# Wacky_Hat_Schematic.net
KiCad netlist of a schematic drawn in Altium Designer
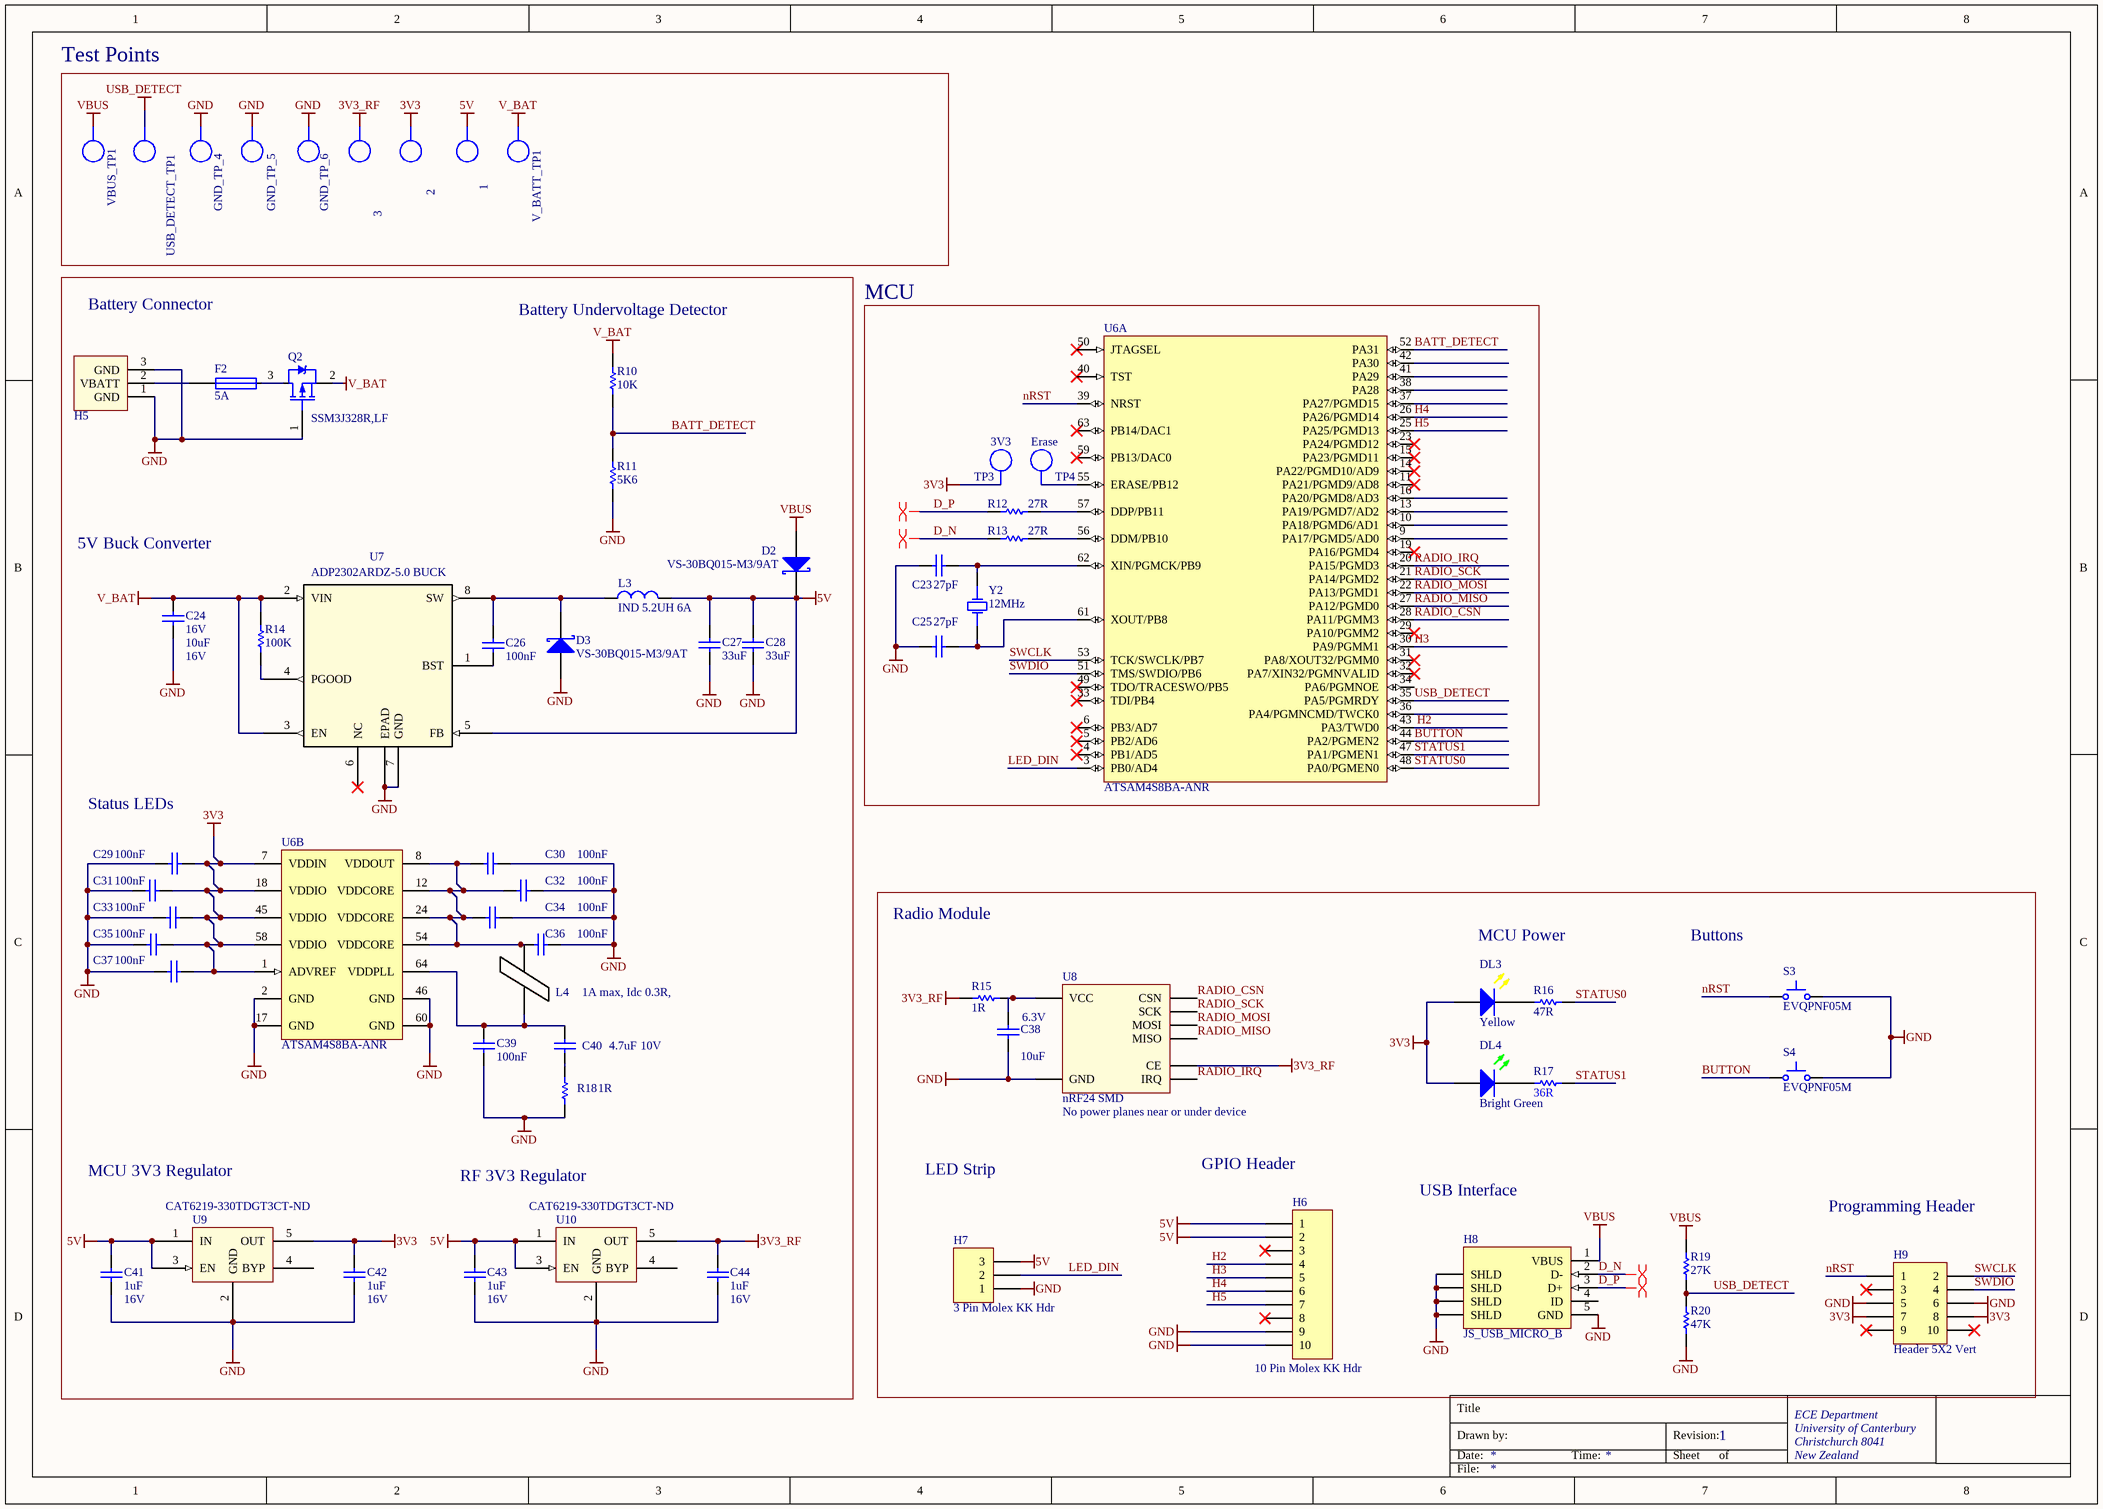
[diagram p0: Wacky Hat Schematic.SchDoc]

(export (version "E")
  (design (tool "Eeschema 10.0.6"))
  (components
    (comp (ref "1")
      (value "TP")
      (footprint "TP_1206")
      (description "Test-Point 3.3x1.6x2.1mm SMD")
      (fields
        (field (name "MANUFACTURER") "Harwin Inc")
        (field (name "MANUFACTURER PART NUMBER") "S1751-46R")
      )
      (libsource (lib "ECE AD19Components_19V1") (part "TP_1206"))
    )
    (comp (ref "2")
      (value "TP")
      (footprint "TP_1206")
      (description "Test-Point 3.3x1.6x2.1mm SMD")
      (fields
        (field (name "MANUFACTURER") "Harwin Inc")
        (field (name "MANUFACTURER PART NUMBER") "S1751-46R")
      )
      (libsource (lib "ECE AD19Components_19V1") (part "TP_1206"))
    )
    (comp (ref "3")
      (value "TP")
      (footprint "TP_1206")
      (description "Test-Point 3.3x1.6x2.1mm SMD")
      (fields
        (field (name "MANUFACTURER") "Harwin Inc")
        (field (name "MANUFACTURER PART NUMBER") "S1751-46R")
      )
      (libsource (lib "ECE AD19Components_19V1") (part "TP_1206"))
    )
    (comp (ref "C23")
      (value "27pF")
      (footprint "CAPC1608L")
      (description "CAP CER 27pF NPO/COG +-5% 50V 0603")
      (libsource (lib "ECE AD19Components_19V1") (part "CC_27pF_0603"))
    )
    (comp (ref "C24")
      (value "10uF")
      (footprint "CAPC2012L")
      (description "CAP CER 10uF X5R 16V 0805")
      (fields
        (field (name "MANUFACTURER") "Samsung Electro-Mechanics")
        (field (name "MANUFACTURER PART NUMBER") "CL21A106KOQNNWE")
        (field (name "VOLTAGE - RATED") "16V")
        (field (name "MAX VOLTAGE") "16V")
      )
      (libsource (lib "ENCE461AD19_19V2") (part "CC_10uF_16V_0805"))
    )
    (comp (ref "C25")
      (value "27pF")
      (footprint "CAPC1608L")
      (description "CAP CER 27pF NPO/COG +-5% 50V 0603")
      (libsource (lib "ECE AD19Components_19V1") (part "CC_27pF_0603"))
    )
    (comp (ref "C26")
      (value "100nF")
      (footprint "CAPC1608L")
      (description "CAP CER 100nF X7R +-10% 50V 0603")
      (libsource (lib "ECE AD19Components_19V1") (part "CC_100nF_0603"))
    )
    (comp (ref "C27")
      (value "33uF")
      (footprint "CAPC2012L")
      (description "CAP CER 33uF X5R 6V3 0805")
      (fields
        (field (name "MANUFACTURER") "TDK Corporation")
        (field (name "MANUFACTURER PART NUMBER") "C2012X5R0J336M125AC")
      )
      (libsource (lib "ENCE461AD19_19V2") (part "CC_33uF_6V3_0805"))
    )
    (comp (ref "C28")
      (value "33uF")
      (footprint "CAPC2012L")
      (description "CAP CER 33uF X5R 6V3 0805")
      (fields
        (field (name "MANUFACTURER") "TDK Corporation")
        (field (name "MANUFACTURER PART NUMBER") "C2012X5R0J336M125AC")
      )
      (libsource (lib "ENCE461AD19_19V2") (part "CC_33uF_6V3_0805"))
    )
    (comp (ref "C29")
      (value "100nF")
      (footprint "CAPC1608L")
      (description "CAP CER 100nF X7R +-10% 50V 0603")
      (libsource (lib "ECE AD19Components_19V1") (part "CC_100nF_0603"))
    )
    (comp (ref "C30")
      (value "100nF")
      (footprint "CAPC1608L")
      (description "CAP CER 100nF X7R +-10% 50V 0603")
      (libsource (lib "ECE AD19Components_19V1") (part "CC_100nF_0603"))
    )
    (comp (ref "C31")
      (value "100nF")
      (footprint "CAPC1608L")
      (description "CAP CER 100nF X7R +-10% 50V 0603")
      (libsource (lib "ECE AD19Components_19V1") (part "CC_100nF_0603"))
    )
    (comp (ref "C32")
      (value "100nF")
      (footprint "CAPC1608L")
      (description "CAP CER 100nF X7R +-10% 50V 0603")
      (libsource (lib "ECE AD19Components_19V1") (part "CC_100nF_0603"))
    )
    (comp (ref "C33")
      (value "100nF")
      (footprint "CAPC1608L")
      (description "CAP CER 100nF X7R +-10% 50V 0603")
      (libsource (lib "ECE AD19Components_19V1") (part "CC_100nF_0603"))
    )
    (comp (ref "C34")
      (value "100nF")
      (footprint "CAPC1608L")
      (description "CAP CER 100nF X7R +-10% 50V 0603")
      (libsource (lib "ECE AD19Components_19V1") (part "CC_100nF_0603"))
    )
    (comp (ref "C35")
      (value "100nF")
      (footprint "CAPC1608L")
      (description "CAP CER 100nF X7R +-10% 50V 0603")
      (libsource (lib "ECE AD19Components_19V1") (part "CC_100nF_0603"))
    )
    (comp (ref "C36")
      (value "100nF")
      (footprint "CAPC1608L")
      (description "CAP CER 100nF X7R +-10% 50V 0603")
      (libsource (lib "ECE AD19Components_19V1") (part "CC_100nF_0603"))
    )
    (comp (ref "C37")
      (value "100nF")
      (footprint "CAPC1608L")
      (description "CAP CER 100nF X7R +-10% 50V 0603")
      (libsource (lib "ECE AD19Components_19V1") (part "CC_100nF_0603"))
    )
    (comp (ref "C38")
      (value "10uF")
      (footprint "CAPC1608L")
      (description "CAP CER 10UF X5R +-20% 6V3 0603")
      (fields (field (name "VOLTAGE - RATED") "6.3V"))
      (libsource (lib "ECE AD19Components_19V1") (part "CC_10uF_0603"))
    )
    (comp (ref "C39")
      (value "100nF")
      (footprint "CAPC1608L")
      (description "CAP CER 100nF X7R +-10% 50V 0603")
      (libsource (lib "ECE AD19Components_19V1") (part "CC_100nF_0603"))
    )
    (comp (ref "C40")
      (value "4.7uF")
      (footprint "CAPC1608N")
      (description "CAP CER 4.7uF X5R +-20%  10V 0603")
      (fields (field (name "MAX VOLTAGE") "10V"))
      (libsource (lib "ECE AD19Components_19V1") (part "CC_4.7uF_0603"))
    )
    (comp (ref "C41")
      (value "1uF")
      (footprint "CAPC1608L")
      (description "CAP CER 1uF Y5V -20% +80% 16V 0603")
      (fields (field (name "MAX VOLTAGE") "16V"))
      (libsource (lib "ECE AD19Components_19V1") (part "CC_1uF_0603"))
    )
    (comp (ref "C42")
      (value "1uF")
      (footprint "CAPC1608L")
      (description "CAP CER 1uF Y5V -20% +80% 16V 0603")
      (fields (field (name "MAX VOLTAGE") "16V"))
      (libsource (lib "ECE AD19Components_19V1") (part "CC_1uF_0603"))
    )
    (comp (ref "C43")
      (value "1uF")
      (footprint "CAPC1608L")
      (description "CAP CER 1uF Y5V -20% +80% 16V 0603")
      (fields (field (name "MAX VOLTAGE") "16V"))
      (libsource (lib "ECE AD19Components_19V1") (part "CC_1uF_0603"))
    )
    (comp (ref "C44")
      (value "1uF")
      (footprint "CAPC1608L")
      (description "CAP CER 1uF Y5V -20% +80% 16V 0603")
      (fields (field (name "MAX VOLTAGE") "16V"))
      (libsource (lib "ECE AD19Components_19V1") (part "CC_1uF_0603"))
    )
    (comp (ref "D2")
      (value "VS-30BQ015-M3/9AT")
      (footprint "SMC")
      (description "DIODE, SCHOTTKY, 3A, 15V, DO-214AB / SMC")
      (fields (field (name "MANUFACTURER") "Vishay Semiconductors"))
      (libsource (lib "ECE AD19Components_19V1") (part "DS_VS-30BQ015-M3"))
    )
    (comp (ref "D3")
      (value "VS-30BQ015-M3/9AT")
      (footprint "SMC")
      (description "DIODE, SCHOTTKY, 3A, 15V, DO-214AB / SMC")
      (fields (field (name "MANUFACTURER") "Vishay Semiconductors"))
      (libsource (lib "ECE AD19Components_19V1") (part "DS_VS-30BQ015-M3"))
    )
    (comp (ref "DL3")
      (value "Yellow")
      (footprint "WL-SMCW0603")
      (description "LED Yellow 120mcd 0603 SMD")
      (fields
        (field (name "MANUFACTURER") "WURTH ELEKTRONIK")
        (field (name "MANUFACTURER PART NUMBER") "150060YS75000")
        (field (name "LED COLOUR") "Yellow")
      )
      (libsource (lib "ECE AD19Components_19V1") (part "DL_150060YS75000"))
    )
    (comp (ref "DL4")
      (value "Bright Green")
      (footprint "WL-SMCW0603")
      (description "LED Bright Green 40mcd 0603 SMD")
      (fields
        (field (name "MANUFACTURER") "WURTH ELEKTRONIK")
        (field (name "MANUFACTURER PART NUMBER") "150060VS75000")
        (field (name "LED COLOUR") "Bright Green")
      )
      (libsource (lib "ECE AD19Components_19V1") (part "DL_150060VS75000"))
    )
    (comp (ref "F2")
      (value "5A")
      (footprint "RESC3216N")
      (description "Fuse 5.0A Fast Acting 1206 SMD")
      (fields (field (name "MANUFACTURER PART NUMBER") "C1F5") (field (name "MANUFACTURER") "Bel TRP"))
      (libsource (lib "ECE AD19Components_19V1") (part "FS_Fuse_5.0A"))
    )
    (comp (ref "GND_TP_4")
      (value "TP")
      (footprint "TP_1206")
      (description "Test-Point 3.3x1.6x2.1mm SMD")
      (fields
        (field (name "MANUFACTURER") "Harwin Inc")
        (field (name "MANUFACTURER PART NUMBER") "S1751-46R")
      )
      (libsource (lib "ECE AD19Components_19V1") (part "TP_1206"))
    )
    (comp (ref "GND_TP_5")
      (value "TP")
      (footprint "TP_1206")
      (description "Test-Point 3.3x1.6x2.1mm SMD")
      (fields
        (field (name "MANUFACTURER") "Harwin Inc")
        (field (name "MANUFACTURER PART NUMBER") "S1751-46R")
      )
      (libsource (lib "ECE AD19Components_19V1") (part "TP_1206"))
    )
    (comp (ref "GND_TP_6")
      (value "TP")
      (footprint "TP_1206")
      (description "Test-Point 3.3x1.6x2.1mm SMD")
      (fields
        (field (name "MANUFACTURER") "Harwin Inc")
        (field (name "MANUFACTURER PART NUMBER") "S1751-46R")
      )
      (libsource (lib "ECE AD19Components_19V1") (part "TP_1206"))
    )
    (comp (ref "H5")
      (value "Battery_HEADER_3pin")
      (footprint "BATT_HEADER_3POS")
      (description "3Pin Header 2.54mm spacing")
      (libsource (lib "ENCE461AD19_19V2") (part "Battery_HEADER_3pin"))
    )
    (comp (ref "H6")
      (value "10 Pin Molex KK Hdr")
      (footprint "MOLEX_KK_10_HDR")
      (description "CONN HEADER 10POS 2.54mm VERT_ Thru Hole")
      (libsource (lib "ECE AD19Components_19V1") (part "JA_MOLEX_KK_10POS"))
    )
    (comp (ref "H7")
      (value "3 Pin Molex KK Hdr")
      (footprint "MOLEX_KK_3_HDR")
      (description "CONN HEADER 3POS 2.54mm VERT_Thru Hole")
      (fields (field (name "MANUFACTURER") "Molex"))
      (libsource (lib "ECE AD19Components_19V1") (part "JA_MOLEX_KK_3POS"))
    )
    (comp (ref "H8")
      (value "JS_USB_MICRO_B")
      (footprint "FCI_USB_10118194-0001LF")
      (description "CONN USB MICRO B RECPT SMT R/A")
      (fields (field (name "MANUFACTURER") "FCI") (field (name "MANUFACTURER PART NUMBER") "10118194-0001LF"))
      (libsource (lib "ECE AD19Components_19V1") (part "JS_USB_MICRO_B_SMT"))
    )
    (comp (ref "H9")
      (value "Header 5X2 Vert")
      (footprint "IDC2.54-V10D")
      (description "IDC Header, 2,54mm, 10-Pin, Vert")
      (libsource (lib "ECE AD19Components_19V1") (part "JA_HDR_IDC_5X2_VERT"))
    )
    (comp (ref "L3")
      (value "IND 5.2UH 6A")
      (footprint "INDUCTOR5u2")
      (description "FIXED IND 5.2UH 6A 22 MOHM SMD")
      (fields
        (field (name "MANUFACTURER") "Sumida America Components Inc.")
        (field (name "MANUFACTURER PART NUMBER") "CDRH104RNP-5R2NC")
      )
      (libsource (lib "ENCE461AD19_19V2") (part "CDRH104RNP-5R2NC"))
    )
    (comp (ref "L4")
      (value "1A max, Idc 0.3R,")
      (footprint "INDC3216L")
      (description "Ferrite Bead, Rdc 0.3R, Z100MHZ 600R, Imax 1A, SMD 1206")
      (fields
        (field (name "MANUFACTURER") "FAIR-RITE")
        (field (name "MANUFACTURER PART NUMBER") "2512066017Y1")
      )
      (libsource (lib "ECE AD19Components_19V1") (part "IN_Ferrite-Bead"))
    )
    (comp (ref "Q2")
      (value "SSM3J328R,LF")
      (footprint "SOT23_L")
      (description "MOSFET P-CH 20V 6A SOT23-3")
      (fields
        (field (name "MANUFACTURER") "Toshiba")
        (field (name "MANUFACTURER PART NUMBER") "SSM3J328R,LF")
      )
      (libsource (lib "ECE AD19Components_19V1") (part "TM_SSM3J328R"))
    )
    (comp (ref "R10")
      (value "10K")
      (footprint "RESC1608L")
      (description "RES 10.0K OHM 1/10W 5% 0603 SMD")
      (libsource (lib "ECE AD19Components_19V1") (part "RS_10K"))
    )
    (comp (ref "R11")
      (value "5K6")
      (footprint "RESC1608L")
      (description "RES 5.6K OHM 1/10W 5% 0603 SMD")
      (libsource (lib "ECE AD19Components_19V1") (part "RS_5K6"))
    )
    (comp (ref "R12")
      (value "27R")
      (footprint "RESC1608L")
      (description "RES 27 OHM 1/10W 5% 0603 SMD")
      (libsource (lib "ECE AD19Components_19V1") (part "RS_27R"))
    )
    (comp (ref "R13")
      (value "27R")
      (footprint "RESC1608L")
      (description "RES 27 OHM 1/10W 5% 0603 SMD")
      (libsource (lib "ECE AD19Components_19V1") (part "RS_27R"))
    )
    (comp (ref "R14")
      (value "100K")
      (footprint "RESC1608L")
      (description "RES 100K OHM 1/10W 5% 0603 SMD")
      (libsource (lib "ECE AD19Components_19V1") (part "RS_100K"))
    )
    (comp (ref "R15")
      (value "1R")
      (footprint "RESC3216L")
      (description "RES 1R OHM 1/4W 5% 1206 SMD")
      (libsource (lib "ECE AD19Components_19V1") (part "RT_1R"))
    )
    (comp (ref "R16")
      (value "47R")
      (footprint "RESC1608L")
      (description "RES 47 OHM 1/10W 5% 0603 SMD")
      (libsource (lib "ECE AD19Components_19V1") (part "RS_47R"))
    )
    (comp (ref "R17")
      (value "36R")
      (footprint "RESC1608L")
      (description "RES 36 OHM 1/10W 5% 0603 SMD")
      (libsource (lib "ECE AD19Components_19V1") (part "RS_36R"))
    )
    (comp (ref "R18")
      (value "1R")
      (footprint "RESC3216L")
      (description "RES 1R OHM 1/4W 5% 1206 SMD")
      (libsource (lib "ECE AD19Components_19V1") (part "RT_1R"))
    )
    (comp (ref "R19")
      (value "27K")
      (footprint "RESC1608L")
      (description "RES 27K OHM 1/10W 5% 0603 SMD")
      (libsource (lib "ECE AD19Components_19V1") (part "RS_27K"))
    )
    (comp (ref "R20")
      (value "47K")
      (footprint "RESC1608N")
      (description "RES 47.0K OHM 1/10W 5% 0603 SMD")
      (libsource (lib "ECE AD19Components_19V1") (part "RS_47K"))
    )
    (comp (ref "S3")
      (value "EVQPNF05M")
      (footprint "EVQPNF05M")
      (description "Panasonic 6 x 3.5mm SMD Light Touch Switch Type SMD")
      (fields (field (name "MANUFACTURER") "Panasonic"))
      (libsource (lib "ECE AD19Components_19V1") (part "WS_EVQPNF05M"))
    )
    (comp (ref "S4")
      (value "EVQPNF05M")
      (footprint "EVQPNF05M")
      (description "Panasonic 6 x 3.5mm SMD Light Touch Switch Type SMD")
      (fields (field (name "MANUFACTURER") "Panasonic"))
      (libsource (lib "ECE AD19Components_19V1") (part "WS_EVQPNF05M"))
    )
    (comp (ref "TP3")
      (value "3V3")
      (footprint "TP_1206")
      (description "Test-Point 3.3x1.6x2.1mm SMD")
      (fields
        (field (name "MANUFACTURER") "Harwin Inc")
        (field (name "MANUFACTURER PART NUMBER") "S1751-46R")
      )
      (libsource (lib "ECE AD19Components_19V1") (part "TP_1206"))
    )
    (comp (ref "TP4")
      (value "Erase")
      (footprint "TP_1206")
      (description "Test-Point 3.3x1.6x2.1mm SMD")
      (fields
        (field (name "MANUFACTURER") "Harwin Inc")
        (field (name "MANUFACTURER PART NUMBER") "S1751-46R")
      )
      (libsource (lib "ECE AD19Components_19V1") (part "TP_1206"))
    )
    (comp (ref "U6")
      (value "ATSAM4S8BA-ANR")
      (footprint "LQFP64_L")
      (description "IC MCU 32BIT 512KB FLASH 64LQFP")
      (fields (field (name "MANUFACTURER") "Atmel"))
      (libsource (lib "ECE AD19Components_19V1") (part "SE_ATSAM4S16BA-MU"))
    )
    (comp (ref "U7")
      (value "ADP2302ARDZ-5.0 BUCK")
      (footprint "RD_8_1")
      (description "IC REG BUCK 5V 2A 8SOIC")
      (fields (field (name "MANUFACTURER_PART_NUMBER") "ADP2302ARDZ-5.0-R7"))
      (libsource (lib "ENCE461AD19_19V2") (part "ADP2302ARDZ-5.0-R7"))
    )
    (comp (ref "U8")
      (value "nRF24 SMD")
      (footprint "NRF24")
      (description "nRF24 SMD Module")
      (fields (field (name "WARNING") "No power planes near or under device"))
      (libsource (lib "ENCE461AD19_19V2") (part "NRF24"))
    )
    (comp (ref "U9")
      (value "CAT6219-330TDGT3")
      (footprint "SOT95P280X145-5N")
      (description "IC REG LIN 3.3V 500MA TSOT23-5")
      (fields
        (field (name "BASE PART NUMBER") "CAT6219")
        (field (name "SUPPLIER PART NUMBER") "CAT6219-330TDGT3CT-ND")
      )
      (libsource (lib "ENCE461AD19_19V2") (part "SV_CAT6219-330TDGT3"))
    )
    (comp (ref "U10")
      (value "CAT6219-330TDGT3")
      (footprint "SOT95P280X145-5N")
      (description "IC REG LIN 3.3V 500MA TSOT23-5")
      (fields
        (field (name "BASE PART NUMBER") "CAT6219")
        (field (name "SUPPLIER PART NUMBER") "CAT6219-330TDGT3CT-ND")
      )
      (libsource (lib "ENCE461AD19_19V2") (part "SV_CAT6219-330TDGT3"))
    )
    (comp (ref "USB_DETECT_TP1")
      (value "TP")
      (footprint "TP_1206")
      (description "Test-Point 3.3x1.6x2.1mm SMD")
      (fields
        (field (name "MANUFACTURER") "Harwin Inc")
        (field (name "MANUFACTURER PART NUMBER") "S1751-46R")
      )
      (libsource (lib "ECE AD19Components_19V1") (part "TP_1206"))
    )
    (comp (ref "VBUS_TP1")
      (value "TP")
      (footprint "TP_1206")
      (description "Test-Point 3.3x1.6x2.1mm SMD")
      (fields
        (field (name "MANUFACTURER") "Harwin Inc")
        (field (name "MANUFACTURER PART NUMBER") "S1751-46R")
      )
      (libsource (lib "ECE AD19Components_19V1") (part "TP_1206"))
    )
    (comp (ref "V_BATT_TP1")
      (value "TP")
      (footprint "TP_1206")
      (description "Test-Point 3.3x1.6x2.1mm SMD")
      (fields
        (field (name "MANUFACTURER") "Harwin Inc")
        (field (name "MANUFACTURER PART NUMBER") "S1751-46R")
      )
      (libsource (lib "ECE AD19Components_19V1") (part "TP_1206"))
    )
    (comp (ref "Y2")
      (value "12MHz")
      (footprint "6.0X3.5-4")
      (description "CRYSTAL 12MHZ 18PF 6X3.5mm SMD")
      (fields
        (field (name "MANUFACTURER") "CTS-Frequency Controls")
        (field (name "MANUFACTURER PART NUMBER") "406C35D12M00000")
        (field (name "FREQUENCY") "12MHz")
      )
      (libsource (lib "ECE AD19Components_19V1") (part "XT_CRYSTAL_12MHz_18pF"))
    )
  )
  (nets
    (net (code "1") (name "/BATT_DETECT") (class "Default")
      (node (ref "R10") (pin "1") (pinfunction "1_1") (pintype "passive"))
      (node (ref "R11") (pin "2") (pinfunction "2_2") (pintype "passive"))
      (node (ref "U6") (pin "52") (pinfunction "PA31_52") (pintype "bidirectional"))
    )
    (net (code "2") (name "/BUTTON") (class "Default")
      (node (ref "S4") (pin "1") (pintype "passive"))
      (node (ref "U6") (pin "44") (pinfunction "PA2/PGMEN2_44") (pintype "bidirectional"))
    )
    (net (code "3") (name "/D_N") (class "Default")
      (node (ref "H8") (pin "2") (pinfunction "D-_2") (pintype "input"))
      (node (ref "R13") (pin "1") (pinfunction "1_1") (pintype "passive"))
    )
    (net (code "4") (name "/D_P") (class "Default")
      (node (ref "H8") (pin "3") (pinfunction "D+_3") (pintype "input"))
      (node (ref "R12") (pin "1") (pinfunction "1_1") (pintype "passive"))
    )
    (net (code "5") (name "/H2") (class "Default")
      (node (ref "H6") (pin "4") (pinfunction "4_4") (pintype "passive"))
      (node (ref "U6") (pin "43") (pinfunction "PA3/TWD0_43") (pintype "bidirectional"))
    )
    (net (code "6") (name "/H3") (class "Default")
      (node (ref "H6") (pin "5") (pinfunction "5_5") (pintype "passive"))
      (node (ref "U6") (pin "30") (pinfunction "PA9/PGMM1_30") (pintype "bidirectional"))
    )
    (net (code "7") (name "/H4") (class "Default")
      (node (ref "H6") (pin "6") (pinfunction "6_6") (pintype "passive"))
      (node (ref "U6") (pin "26") (pinfunction "PA26/PGMD14_26") (pintype "bidirectional"))
    )
    (net (code "8") (name "/H5") (class "Default")
      (node (ref "H6") (pin "7") (pinfunction "7_7") (pintype "passive"))
      (node (ref "U6") (pin "25") (pinfunction "PA25/PGMD13_25") (pintype "bidirectional"))
    )
    (net (code "9") (name "/LED_DIN") (class "Default")
      (node (ref "H7") (pin "2") (pinfunction "2_2") (pintype "passive"))
      (node (ref "U6") (pin "3") (pinfunction "PB0/AD4_3") (pintype "bidirectional"))
    )
    (net (code "10") (name "/RADIO_CSN") (class "Default")
      (node (ref "U6") (pin "28") (pinfunction "PA11/PGMM3_28") (pintype "bidirectional"))
      (node (ref "U8") (pin "4") (pinfunction "CSN_4") (pintype "passive"))
    )
    (net (code "11") (name "/RADIO_IRQ") (class "Default")
      (node (ref "U6") (pin "20") (pinfunction "PA15/PGMD3_20") (pintype "bidirectional"))
      (node (ref "U8") (pin "8") (pinfunction "IRQ_8") (pintype "passive"))
    )
    (net (code "12") (name "/RADIO_MISO") (class "Default")
      (node (ref "U6") (pin "27") (pinfunction "PA12/PGMD0_27") (pintype "bidirectional"))
      (node (ref "U8") (pin "7") (pinfunction "MISO_7") (pintype "passive"))
    )
    (net (code "13") (name "/RADIO_MOSI") (class "Default")
      (node (ref "U6") (pin "22") (pinfunction "PA13/PGMD1_22") (pintype "bidirectional"))
      (node (ref "U8") (pin "6") (pinfunction "MOSI_6") (pintype "passive"))
    )
    (net (code "14") (name "/RADIO_SCK") (class "Default")
      (node (ref "U6") (pin "21") (pinfunction "PA14/PGMD2_21") (pintype "bidirectional"))
      (node (ref "U8") (pin "5") (pinfunction "SCK_5") (pintype "passive"))
    )
    (net (code "15") (name "/STATUS0") (class "Default")
      (node (ref "R16") (pin "2") (pinfunction "2_2") (pintype "passive"))
      (node (ref "U6") (pin "48") (pinfunction "PA0/PGMEN0_48") (pintype "bidirectional"))
    )
    (net (code "16") (name "/STATUS1") (class "Default")
      (node (ref "R17") (pin "2") (pinfunction "2_2") (pintype "passive"))
      (node (ref "U6") (pin "47") (pinfunction "PA1/PGMEN1_47") (pintype "bidirectional"))
    )
    (net (code "17") (name "/SWCLK") (class "Default")
      (node (ref "H9") (pin "2") (pinfunction "2_2") (pintype "passive"))
      (node (ref "U6") (pin "53") (pinfunction "TCK/SWCLK/PB7_53") (pintype "bidirectional"))
    )
    (net (code "18") (name "/SWDIO") (class "Default")
      (node (ref "H9") (pin "4") (pinfunction "4_4") (pintype "passive"))
      (node (ref "U6") (pin "51") (pinfunction "TMS/SWDIO/PB6_51") (pintype "bidirectional"))
    )
    (net (code "19") (name "/nRST") (class "Default")
      (node (ref "H9") (pin "1") (pinfunction "1_1") (pintype "passive"))
      (node (ref "S3") (pin "1") (pintype "passive"))
      (node (ref "U6") (pin "39") (pinfunction "NRST_39") (pintype "bidirectional"))
    )
    (net (code "20") (name "3V3") (class "Default")
      (node (ref "2") (pin "1") (pinfunction "1_1") (pintype "passive"))
      (node (ref "C29") (pin "2") (pinfunction "2_2") (pintype "passive"))
      (node (ref "C31") (pin "2") (pinfunction "2_2") (pintype "passive"))
      (node (ref "C33") (pin "2") (pinfunction "2_2") (pintype "passive"))
      (node (ref "C35") (pin "2") (pinfunction "2_2") (pintype "passive"))
      (node (ref "C37") (pin "2") (pinfunction "2_2") (pintype "passive"))
      (node (ref "C42") (pin "2") (pinfunction "2_2") (pintype "passive"))
      (node (ref "DL3") (pin "2") (pinfunction "A_2") (pintype "passive"))
      (node (ref "DL4") (pin "2") (pinfunction "A_2") (pintype "passive"))
      (node (ref "H9") (pin "7") (pinfunction "7_7") (pintype "passive"))
      (node (ref "H9") (pin "8") (pinfunction "8_8") (pintype "passive"))
      (node (ref "TP3") (pin "1") (pinfunction "1_1") (pintype "passive"))
      (node (ref "U6") (pin "1") (pinfunction "ADVREF_1") (pintype "input"))
      (node (ref "U6") (pin "18") (pinfunction "VDDIO_18") (pintype "power_in"))
      (node (ref "U6") (pin "45") (pinfunction "VDDIO_45") (pintype "power_in"))
      (node (ref "U6") (pin "58") (pinfunction "VDDIO_58") (pintype "power_in"))
      (node (ref "U6") (pin "7") (pinfunction "VDDIN_7") (pintype "power_in"))
      (node (ref "U9") (pin "5") (pinfunction "OUT_5") (pintype "power_in"))
    )
    (net (code "21") (name "3V3_RF") (class "Default")
      (node (ref "3") (pin "1") (pinfunction "1_1") (pintype "passive"))
      (node (ref "C44") (pin "2") (pinfunction "2_2") (pintype "passive"))
      (node (ref "R15") (pin "1") (pinfunction "1_1") (pintype "passive"))
      (node (ref "U10") (pin "5") (pinfunction "OUT_5") (pintype "power_in"))
      (node (ref "U8") (pin "3") (pinfunction "CE_3") (pintype "passive"))
    )
    (net (code "22") (name "5V") (class "Default")
      (node (ref "1") (pin "1") (pinfunction "1_1") (pintype "passive"))
      (node (ref "C27") (pin "2") (pinfunction "2_2") (pintype "passive"))
      (node (ref "C28") (pin "2") (pinfunction "2_2") (pintype "passive"))
      (node (ref "C41") (pin "2") (pinfunction "2_2") (pintype "passive"))
      (node (ref "C43") (pin "2") (pinfunction "2_2") (pintype "passive"))
      (node (ref "D2") (pin "2") (pinfunction "K_2") (pintype "passive"))
      (node (ref "H6") (pin "1") (pinfunction "1_1") (pintype "passive"))
      (node (ref "H6") (pin "2") (pinfunction "2_2") (pintype "passive"))
      (node (ref "H7") (pin "3") (pinfunction "3_3") (pintype "passive"))
      (node (ref "L3") (pin "2") (pintype "passive"))
      (node (ref "U10") (pin "1") (pinfunction "IN_1") (pintype "power_in"))
      (node (ref "U10") (pin "3") (pinfunction "EN_3") (pintype "input"))
      (node (ref "U7") (pin "5") (pinfunction "FB_5") (pintype "input"))
      (node (ref "U9") (pin "1") (pinfunction "IN_1") (pintype "power_in"))
      (node (ref "U9") (pin "3") (pinfunction "EN_3") (pintype "input"))
    )
    (net (code "23") (name "GND") (class "Default")
      (node (ref "C23") (pin "1") (pinfunction "1_1") (pintype "passive"))
      (node (ref "C24") (pin "1") (pinfunction "1_1") (pintype "passive"))
      (node (ref "C25") (pin "1") (pinfunction "1_1") (pintype "passive"))
      (node (ref "C27") (pin "1") (pinfunction "1_1") (pintype "passive"))
      (node (ref "C28") (pin "1") (pinfunction "1_1") (pintype "passive"))
      (node (ref "C29") (pin "1") (pinfunction "1_1") (pintype "passive"))
      (node (ref "C30") (pin "2") (pinfunction "2_2") (pintype "passive"))
      (node (ref "C31") (pin "1") (pinfunction "1_1") (pintype "passive"))
      (node (ref "C32") (pin "2") (pinfunction "2_2") (pintype "passive"))
      (node (ref "C33") (pin "1") (pinfunction "1_1") (pintype "passive"))
      (node (ref "C34") (pin "2") (pinfunction "2_2") (pintype "passive"))
      (node (ref "C35") (pin "1") (pinfunction "1_1") (pintype "passive"))
      (node (ref "C36") (pin "2") (pinfunction "2_2") (pintype "passive"))
      (node (ref "C37") (pin "1") (pinfunction "1_1") (pintype "passive"))
      (node (ref "C38") (pin "1") (pinfunction "1_1") (pintype "passive"))
      (node (ref "C39") (pin "1") (pinfunction "1_1") (pintype "passive"))
      (node (ref "C41") (pin "1") (pinfunction "1_1") (pintype "passive"))
      (node (ref "C42") (pin "1") (pinfunction "1_1") (pintype "passive"))
      (node (ref "C43") (pin "1") (pinfunction "1_1") (pintype "passive"))
      (node (ref "C44") (pin "1") (pinfunction "1_1") (pintype "passive"))
      (node (ref "D3") (pin "1") (pinfunction "A_1") (pintype "passive"))
      (node (ref "GND_TP_4") (pin "1") (pinfunction "1_1") (pintype "passive"))
      (node (ref "GND_TP_5") (pin "1") (pinfunction "1_1") (pintype "passive"))
      (node (ref "GND_TP_6") (pin "1") (pinfunction "1_1") (pintype "passive"))
      (node (ref "H5") (pin "1") (pinfunction "GND_1") (pintype "passive"))
      (node (ref "H5") (pin "3") (pinfunction "GND_3") (pintype "passive"))
      (node (ref "H6") (pin "10") (pinfunction "10_10") (pintype "passive"))
      (node (ref "H6") (pin "9") (pinfunction "9_9") (pintype "passive"))
      (node (ref "H7") (pin "1") (pinfunction "1_1") (pintype "passive"))
      (node (ref "H8") (pin "5") (pinfunction "GND_5") (pintype "passive"))
      (node (ref "H8") (pin "6") (pinfunction "SHLD_6") (pintype "passive"))
      (node (ref "H9") (pin "5") (pinfunction "5_5") (pintype "passive"))
      (node (ref "H9") (pin "6") (pinfunction "6_6") (pintype "passive"))
      (node (ref "Q2") (pin "1") (pinfunction "1_1") (pintype "passive"))
      (node (ref "R11") (pin "1") (pinfunction "1_1") (pintype "passive"))
      (node (ref "R18") (pin "1") (pinfunction "1_1") (pintype "passive"))
      (node (ref "R20") (pin "1") (pinfunction "1_1") (pintype "passive"))
      (node (ref "S3") (pin "2") (pintype "passive"))
      (node (ref "S4") (pin "2") (pintype "passive"))
      (node (ref "U10") (pin "2") (pinfunction "GND_2") (pintype "power_in"))
      (node (ref "U6") (pin "17") (pinfunction "GND_17") (pintype "power_in"))
      (node (ref "U6") (pin "2") (pinfunction "GND_2") (pintype "power_in"))
      (node (ref "U6") (pin "46") (pinfunction "GND_46") (pintype "power_in"))
      (node (ref "U6") (pin "60") (pinfunction "GND_60") (pintype "power_in"))
      (node (ref "U7") (pin "7") (pinfunction "GND_7") (pintype "power_in"))
      (node (ref "U7") (pin "EPAD") (pinfunction "EPAD_EPAD") (pintype "passive"))
      (node (ref "U8") (pin "2") (pinfunction "GND_2") (pintype "passive"))
      (node (ref "U9") (pin "2") (pinfunction "GND_2") (pintype "power_in"))
    )
    (net (code "24") (name "Net-(C40-Pad1)") (class "Default")
      (node (ref "C40") (pin "1") (pinfunction "1_1") (pintype "passive"))
      (node (ref "R18") (pin "2") (pinfunction "2_2") (pintype "passive"))
    )
    (net (code "25") (name "Net-(D3-K)") (class "Default")
      (node (ref "C26") (pin "2") (pinfunction "2_2") (pintype "passive"))
      (node (ref "D3") (pin "2") (pinfunction "K_2") (pintype "passive"))
      (node (ref "L3") (pin "1") (pintype "passive"))
      (node (ref "U7") (pin "8") (pinfunction "SW_8") (pintype "output"))
    )
    (net (code "26") (name "Net-(DL3-K)") (class "Default")
      (node (ref "DL3") (pin "1") (pinfunction "K_1") (pintype "passive"))
      (node (ref "R16") (pin "1") (pinfunction "1_1") (pintype "passive"))
    )
    (net (code "27") (name "Net-(DL4-K)") (class "Default")
      (node (ref "DL4") (pin "1") (pinfunction "K_1") (pintype "passive"))
      (node (ref "R17") (pin "1") (pinfunction "1_1") (pintype "passive"))
    )
    (net (code "28") (name "Net-(F2-Pad2)") (class "Default")
      (node (ref "F2") (pin "2") (pinfunction "2_2") (pintype "passive"))
      (node (ref "Q2") (pin "3") (pinfunction "3_3") (pintype "passive"))
    )
    (net (code "29") (name "Net-(H5-VBATT)") (class "Default")
      (node (ref "F2") (pin "1") (pinfunction "1_1") (pintype "passive"))
      (node (ref "H5") (pin "2") (pinfunction "VBATT_2") (pintype "passive"))
    )
    (net (code "30") (name "Net-(U6A-DDM{slash}PB10)") (class "Default")
      (node (ref "R13") (pin "2") (pinfunction "2_2") (pintype "passive"))
      (node (ref "U6") (pin "56") (pinfunction "DDM/PB10_56") (pintype "bidirectional"))
    )
    (net (code "31") (name "Net-(U6A-DDP{slash}PB11)") (class "Default")
      (node (ref "R12") (pin "2") (pinfunction "2_2") (pintype "passive"))
      (node (ref "U6") (pin "57") (pinfunction "DDP/PB11_57") (pintype "bidirectional"))
    )
    (net (code "32") (name "Net-(U6A-ERASE{slash}PB12)") (class "Default")
      (node (ref "TP4") (pin "1") (pinfunction "1_1") (pintype "passive"))
      (node (ref "U6") (pin "55") (pinfunction "ERASE/PB12_55") (pintype "bidirectional"))
    )
    (net (code "33") (name "Net-(U6A-XIN{slash}PGMCK{slash}PB9)") (class "Default")
      (node (ref "C23") (pin "2") (pinfunction "2_2") (pintype "passive"))
      (node (ref "U6") (pin "62") (pinfunction "XIN/PGMCK/PB9_62") (pintype "bidirectional"))
      (node (ref "Y2") (pin "1") (pinfunction "OSC1_1") (pintype "passive"))
    )
    (net (code "34") (name "Net-(U6A-XOUT{slash}PB8)") (class "Default")
      (node (ref "C25") (pin "2") (pinfunction "2_2") (pintype "passive"))
      (node (ref "U6") (pin "61") (pinfunction "XOUT/PB8_61") (pintype "bidirectional"))
      (node (ref "Y2") (pin "3") (pinfunction "OSC2_3") (pintype "passive"))
    )
    (net (code "35") (name "Net-(U6B-VDDOUT)") (class "Default")
      (node (ref "C30") (pin "1") (pinfunction "1_1") (pintype "passive"))
      (node (ref "C32") (pin "1") (pinfunction "1_1") (pintype "passive"))
      (node (ref "C34") (pin "1") (pinfunction "1_1") (pintype "passive"))
      (node (ref "C36") (pin "1") (pinfunction "1_1") (pintype "passive"))
      (node (ref "L4") (pin "2") (pinfunction "2_2") (pintype "passive"))
      (node (ref "U6") (pin "12") (pinfunction "VDDCORE_12") (pintype "power_in"))
      (node (ref "U6") (pin "24") (pinfunction "VDDCORE_24") (pintype "power_in"))
      (node (ref "U6") (pin "54") (pinfunction "VDDCORE_54") (pintype "power_in"))
      (node (ref "U6") (pin "8") (pinfunction "VDDOUT_8") (pintype "power_in"))
    )
    (net (code "36") (name "Net-(U6B-VDDPLL)") (class "Default")
      (node (ref "C39") (pin "2") (pinfunction "2_2") (pintype "passive"))
      (node (ref "C40") (pin "2") (pinfunction "2_2") (pintype "passive"))
      (node (ref "L4") (pin "1") (pinfunction "1_1") (pintype "passive"))
      (node (ref "U6") (pin "64") (pinfunction "VDDPLL_64") (pintype "power_in"))
    )
    (net (code "37") (name "Net-(U7-BST)") (class "Default")
      (node (ref "C26") (pin "1") (pinfunction "1_1") (pintype "passive"))
      (node (ref "U7") (pin "1") (pinfunction "BST_1") (pintype "passive"))
    )
    (net (code "38") (name "Net-(U7-PGOOD)") (class "Default")
      (node (ref "R14") (pin "1") (pinfunction "1_1") (pintype "passive"))
      (node (ref "U7") (pin "4") (pinfunction "PGOOD_4") (pintype "output"))
    )
    (net (code "39") (name "Net-(U8-VCC)") (class "Default")
      (node (ref "C38") (pin "2") (pinfunction "2_2") (pintype "passive"))
      (node (ref "R15") (pin "2") (pinfunction "2_2") (pintype "passive"))
      (node (ref "U8") (pin "1") (pinfunction "VCC_1") (pintype "passive"))
    )
    (net (code "40") (name "USB_DETECT") (class "Default")
      (node (ref "R19") (pin "1") (pinfunction "1_1") (pintype "passive"))
      (node (ref "R20") (pin "2") (pinfunction "2_2") (pintype "passive"))
      (node (ref "U6") (pin "35") (pinfunction "PA5/PGMRDY_35") (pintype "bidirectional"))
      (node (ref "USB_DETECT_TP1") (pin "1") (pinfunction "1_1") (pintype "passive"))
    )
    (net (code "41") (name "VBUS") (class "Default")
      (node (ref "D2") (pin "1") (pinfunction "A_1") (pintype "passive"))
      (node (ref "H8") (pin "1") (pinfunction "VBUS_1") (pintype "power_in"))
      (node (ref "R19") (pin "2") (pinfunction "2_2") (pintype "passive"))
      (node (ref "VBUS_TP1") (pin "1") (pinfunction "1_1") (pintype "passive"))
    )
    (net (code "42") (name "V_BAT") (class "Default")
      (node (ref "C24") (pin "2") (pinfunction "2_2") (pintype "passive"))
      (node (ref "Q2") (pin "2") (pinfunction "2_2") (pintype "passive"))
      (node (ref "R10") (pin "2") (pinfunction "2_2") (pintype "passive"))
      (node (ref "R14") (pin "2") (pinfunction "2_2") (pintype "passive"))
      (node (ref "U7") (pin "2") (pinfunction "VIN_2") (pintype "input"))
      (node (ref "U7") (pin "3") (pinfunction "EN_3") (pintype "output"))
      (node (ref "V_BATT_TP1") (pin "1") (pinfunction "1_1") (pintype "passive"))
    )
    (net (code "43") (name "unconnected-(H6-Pad3)") (class "Default")
      (node (ref "H6") (pin "3") (pinfunction "3_3") (pintype "passive+no_connect"))
    )
    (net (code "44") (name "unconnected-(H6-Pad8)") (class "Default")
      (node (ref "H6") (pin "8") (pinfunction "8_8") (pintype "passive+no_connect"))
    )
    (net (code "45") (name "unconnected-(H8-ID-Pad4)") (class "Default")
      (node (ref "H8") (pin "4") (pinfunction "ID_4") (pintype "power_in"))
    )
    (net (code "46") (name "unconnected-(H9-Pad3)") (class "Default")
      (node (ref "H9") (pin "3") (pinfunction "3_3") (pintype "passive+no_connect"))
    )
    (net (code "47") (name "unconnected-(H9-Pad9)") (class "Default")
      (node (ref "H9") (pin "9") (pinfunction "9_9") (pintype "passive+no_connect"))
    )
    (net (code "48") (name "unconnected-(H9-Pad10)") (class "Default")
      (node (ref "H9") (pin "10") (pinfunction "10_10") (pintype "passive+no_connect"))
    )
    (net (code "49") (name "unconnected-(U6A-JTAGSEL-Pad50)") (class "Default")
      (node (ref "U6") (pin "50") (pinfunction "JTAGSEL_50") (pintype "input+no_connect"))
    )
    (net (code "50") (name "unconnected-(U6A-PA4{slash}PGMNCMD{slash}TWCK0-Pad36)") (class "Default")
      (node (ref "U6") (pin "36") (pinfunction "PA4/PGMNCMD/TWCK0_36") (pintype "bidirectional"))
    )
    (net (code "51") (name "unconnected-(U6A-PA6{slash}PGMNOE-Pad34)") (class "Default")
      (node (ref "U6") (pin "34") (pinfunction "PA6/PGMNOE_34") (pintype "bidirectional"))
    )
    (net (code "52") (name "unconnected-(U6A-PA7{slash}XIN32{slash}PGMNVALID-Pad32)") (class "Default")
      (node (ref "U6") (pin "32") (pinfunction "PA7/XIN32/PGMNVALID_32") (pintype "bidirectional+no_connect"))
    )
    (net (code "53") (name "unconnected-(U6A-PA8{slash}XOUT32{slash}PGMM0-Pad31)") (class "Default")
      (node (ref "U6") (pin "31") (pinfunction "PA8/XOUT32/PGMM0_31") (pintype "bidirectional+no_connect"))
    )
    (net (code "54") (name "unconnected-(U6A-PA10{slash}PGMM2-Pad29)") (class "Default")
      (node (ref "U6") (pin "29") (pinfunction "PA10/PGMM2_29") (pintype "bidirectional+no_connect"))
    )
    (net (code "55") (name "unconnected-(U6A-PA16{slash}PGMD4-Pad19)") (class "Default")
      (node (ref "U6") (pin "19") (pinfunction "PA16/PGMD4_19") (pintype "bidirectional+no_connect"))
    )
    (net (code "56") (name "unconnected-(U6A-PA17{slash}PGMD5{slash}AD0-Pad9)") (class "Default")
      (node (ref "U6") (pin "9") (pinfunction "PA17/PGMD5/AD0_9") (pintype "bidirectional"))
    )
    (net (code "57") (name "unconnected-(U6A-PA18{slash}PGMD6{slash}AD1-Pad10)") (class "Default")
      (node (ref "U6") (pin "10") (pinfunction "PA18/PGMD6/AD1_10") (pintype "bidirectional"))
    )
    (net (code "58") (name "unconnected-(U6A-PA19{slash}PGMD7{slash}AD2-Pad13)") (class "Default")
      (node (ref "U6") (pin "13") (pinfunction "PA19/PGMD7/AD2_13") (pintype "bidirectional"))
    )
    (net (code "59") (name "unconnected-(U6A-PA20{slash}PGMD8{slash}AD3-Pad16)") (class "Default")
      (node (ref "U6") (pin "16") (pinfunction "PA20/PGMD8/AD3_16") (pintype "bidirectional"))
    )
    (net (code "60") (name "unconnected-(U6A-PA21{slash}PGMD9{slash}AD8-Pad11)") (class "Default")
      (node (ref "U6") (pin "11") (pinfunction "PA21/PGMD9/AD8_11") (pintype "bidirectional+no_connect"))
    )
    (net (code "61") (name "unconnected-(U6A-PA22{slash}PGMD10{slash}AD9-Pad14)") (class "Default")
      (node (ref "U6") (pin "14") (pinfunction "PA22/PGMD10/AD9_14") (pintype "bidirectional+no_connect"))
    )
    (net (code "62") (name "unconnected-(U6A-PA23{slash}PGMD11-Pad15)") (class "Default")
      (node (ref "U6") (pin "15") (pinfunction "PA23/PGMD11_15") (pintype "bidirectional+no_connect"))
    )
    (net (code "63") (name "unconnected-(U6A-PA24{slash}PGMD12-Pad23)") (class "Default")
      (node (ref "U6") (pin "23") (pinfunction "PA24/PGMD12_23") (pintype "bidirectional+no_connect"))
    )
    (net (code "64") (name "unconnected-(U6A-PA27{slash}PGMD15-Pad37)") (class "Default")
      (node (ref "U6") (pin "37") (pinfunction "PA27/PGMD15_37") (pintype "bidirectional"))
    )
    (net (code "65") (name "unconnected-(U6A-PA28-Pad38)") (class "Default")
      (node (ref "U6") (pin "38") (pinfunction "PA28_38") (pintype "bidirectional"))
    )
    (net (code "66") (name "unconnected-(U6A-PA29-Pad41)") (class "Default")
      (node (ref "U6") (pin "41") (pinfunction "PA29_41") (pintype "bidirectional"))
    )
    (net (code "67") (name "unconnected-(U6A-PA30-Pad42)") (class "Default")
      (node (ref "U6") (pin "42") (pinfunction "PA30_42") (pintype "bidirectional"))
    )
    (net (code "68") (name "unconnected-(U6A-PB1{slash}AD5-Pad4)") (class "Default")
      (node (ref "U6") (pin "4") (pinfunction "PB1/AD5_4") (pintype "bidirectional+no_connect"))
    )
    (net (code "69") (name "unconnected-(U6A-PB2{slash}AD6-Pad5)") (class "Default")
      (node (ref "U6") (pin "5") (pinfunction "PB2/AD6_5") (pintype "bidirectional+no_connect"))
    )
    (net (code "70") (name "unconnected-(U6A-PB3{slash}AD7-Pad6)") (class "Default")
      (node (ref "U6") (pin "6") (pinfunction "PB3/AD7_6") (pintype "bidirectional+no_connect"))
    )
    (net (code "71") (name "unconnected-(U6A-PB13{slash}DAC0-Pad59)") (class "Default")
      (node (ref "U6") (pin "59") (pinfunction "PB13/DAC0_59") (pintype "bidirectional+no_connect"))
    )
    (net (code "72") (name "unconnected-(U6A-PB14{slash}DAC1-Pad63)") (class "Default")
      (node (ref "U6") (pin "63") (pinfunction "PB14/DAC1_63") (pintype "bidirectional+no_connect"))
    )
    (net (code "73") (name "unconnected-(U6A-TDI{slash}PB4-Pad33)") (class "Default")
      (node (ref "U6") (pin "33") (pinfunction "TDI/PB4_33") (pintype "bidirectional+no_connect"))
    )
    (net (code "74") (name "unconnected-(U6A-TDO{slash}TRACESWO{slash}PB5-Pad49)") (class "Default")
      (node (ref "U6") (pin "49") (pinfunction "TDO/TRACESWO/PB5_49") (pintype "bidirectional+no_connect"))
    )
    (net (code "75") (name "unconnected-(U6A-TST-Pad40)") (class "Default")
      (node (ref "U6") (pin "40") (pinfunction "TST_40") (pintype "input+no_connect"))
    )
    (net (code "76") (name "unconnected-(U7-NC-Pad6)") (class "Default")
      (node (ref "U7") (pin "6") (pinfunction "NC_6") (pintype "passive+no_connect"))
    )
    (net (code "77") (name "unconnected-(U9-BYP-Pad4)") (class "Default")
      (node (ref "U9") (pin "4") (pinfunction "BYP_4") (pintype "passive"))
    )
    (net (code "78") (name "unconnected-(U10-BYP-Pad4)") (class "Default")
      (node (ref "U10") (pin "4") (pinfunction "BYP_4") (pintype "passive"))
    )
  )
)
